# LED_light_with_delay_timer.net
KiCad netlist of a schematic drawn in EAGLE
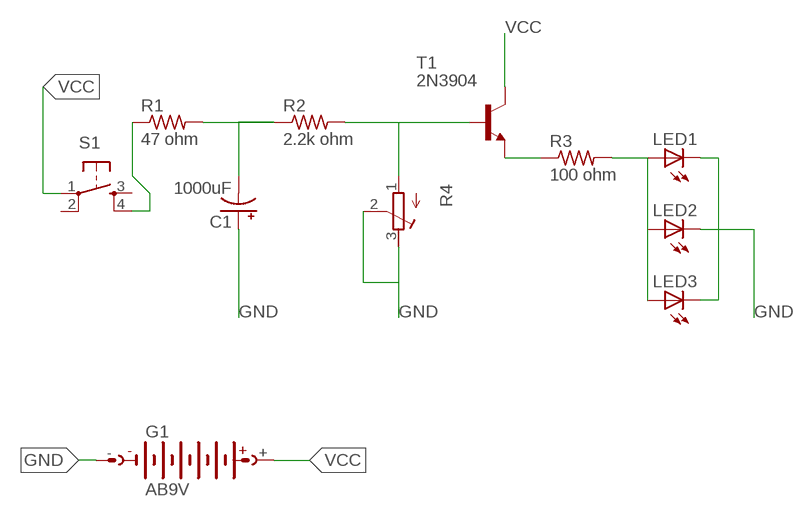
[diagram p0: schematic, sheet 1]

(export (version "E")
  (design (tool "Eeschema 10.0.6"))
  (components
    (comp (ref "C1")
      (value "1000uF")
      (footprint "eagle-import:CPOL-RADIAL-100UF-25V")
      (libsource (lib "eagle-import") (part "CAP_POLPTH1"))
    )
    (comp (ref "G1")
      (value "AB9V")
      (footprint "eagle-import:AB9V")
      (libsource (lib "eagle-import") (part "AB9V"))
    )
    (comp (ref "LED1")
      (value "LED5MM")
      (footprint "eagle-import:LED5MM")
      (libsource (lib "eagle-import") (part "LED5MM"))
    )
    (comp (ref "LED2")
      (value "LED5MM")
      (footprint "eagle-import:LED5MM")
      (libsource (lib "eagle-import") (part "LED5MM"))
    )
    (comp (ref "LED3")
      (value "LED5MM")
      (footprint "eagle-import:LED5MM")
      (libsource (lib "eagle-import") (part "LED5MM"))
    )
    (comp (ref "R1")
      (value "47 ohm")
      (footprint "eagle-import:0204_7")
      (libsource (lib "eagle-import") (part "R-US_0204/7"))
    )
    (comp (ref "R2")
      (value "2.2k ohm")
      (footprint "eagle-import:0204_7")
      (libsource (lib "eagle-import") (part "R-US_0204/7"))
    )
    (comp (ref "R3")
      (value "100 ohm")
      (footprint "eagle-import:0204_7")
      (libsource (lib "eagle-import") (part "R-US_0204/7"))
    )
    (comp (ref "R4")
      (value "R-TRIMM3339P")
      (footprint "eagle-import:RTRIM3339P")
      (libsource (lib "eagle-import") (part "R-TRIMM3339P"))
    )
    (comp (ref "S1")
      (value "TAC_SWITCHPTH")
      (footprint "eagle-import:TACTILE-PTH")
      (libsource (lib "eagle-import") (part "TAC_SWITCHPTH"))
    )
    (comp (ref "T1")
      (value "2N3904")
      (footprint "eagle-import:TO92")
      (libsource (lib "eagle-import") (part "2N3904"))
    )
  )
  (nets
    (net (code "1") (name "GND") (class "Default")
      (node (ref "C1") (pin "1") (pinfunction "+_1") (pintype "passive"))
      (node (ref "G1") (pin "-") (pinfunction "-_-") (pintype "passive"))
      (node (ref "LED1") (pin "K") (pinfunction "C_K") (pintype "passive"))
      (node (ref "LED2") (pin "K") (pinfunction "C_K") (pintype "passive"))
      (node (ref "LED3") (pin "K") (pinfunction "C_K") (pintype "passive"))
      (node (ref "R4") (pin "2") (pinfunction "S_2") (pintype "passive"))
      (node (ref "R4") (pin "3") (pinfunction "E_3") (pintype "passive"))
    )
    (net (code "2") (name "Net-(C1--)") (class "Default")
      (node (ref "C1") (pin "2") (pinfunction "-_2") (pintype "passive"))
      (node (ref "R1") (pin "2") (pinfunction "2_2") (pintype "passive"))
      (node (ref "R2") (pin "1") (pinfunction "1_1") (pintype "passive"))
    )
    (net (code "3") (name "Net-(LED1-PadA)") (class "Default")
      (node (ref "LED1") (pin "A") (pinfunction "A_A") (pintype "passive"))
      (node (ref "LED2") (pin "A") (pinfunction "A_A") (pintype "passive"))
      (node (ref "LED3") (pin "A") (pinfunction "A_A") (pintype "passive"))
      (node (ref "R3") (pin "2") (pinfunction "2_2") (pintype "passive"))
    )
    (net (code "4") (name "Net-(R1-Pad1)") (class "Default")
      (node (ref "R1") (pin "1") (pinfunction "1_1") (pintype "passive"))
      (node (ref "S1") (pin "4") (pinfunction "4_4") (pintype "passive"))
    )
    (net (code "5") (name "Net-(R4-A)") (class "Default")
      (node (ref "R2") (pin "2") (pinfunction "2_2") (pintype "passive"))
      (node (ref "R4") (pin "1") (pinfunction "A_1") (pintype "passive"))
      (node (ref "T1") (pin "2") (pinfunction "B_2") (pintype "passive"))
    )
    (net (code "6") (name "Net-(T1-E)") (class "Default")
      (node (ref "R3") (pin "1") (pinfunction "1_1") (pintype "passive"))
      (node (ref "T1") (pin "3") (pinfunction "E_3") (pintype "passive"))
    )
    (net (code "7") (name "VCC") (class "Default")
      (node (ref "G1") (pin "+") (pinfunction "+_+") (pintype "passive"))
      (node (ref "S1") (pin "1") (pinfunction "1_1") (pintype "passive"))
      (node (ref "T1") (pin "1") (pinfunction "C_1") (pintype "passive"))
    )
    (net (code "8") (name "unconnected-(S1-Pad2)") (class "Default")
      (node (ref "S1") (pin "2") (pinfunction "2_2") (pintype "passive"))
    )
    (net (code "9") (name "unconnected-(S1-Pad3)") (class "Default")
      (node (ref "S1") (pin "3") (pinfunction "3_3") (pintype "passive"))
    )
  )
)
